# Interfaces.net
KiCad netlist of a schematic drawn in Altium Designer
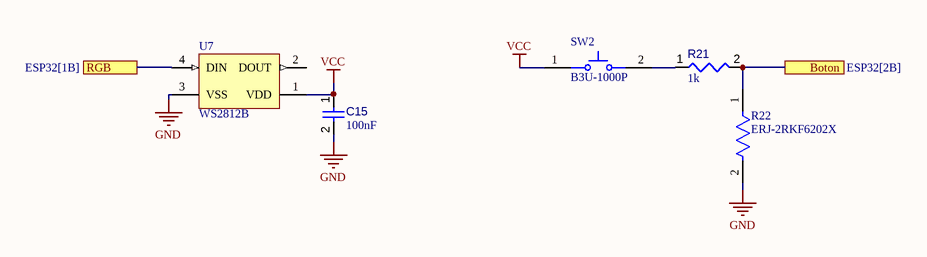
[diagram p0: Interfaces.SchDoc]

(export (version "E")
  (design (tool "Eeschema 10.0.6"))
  (components
    (comp (ref "C15")
      (value "100nF")
      (footprint "CAPC1005X56X25LL10T15")
      (description "Chip Capacitor, 0.1 uF, +/- 5%, 16 V, 0402 (1005 Metric)")
      (fields (field (name "TOLERANCE") "5%") (field (name "Comment") "Capacitor 0.1 uF +/- 5% 16 V 0402"))
      (libsource (lib "Own Worskpace") (part "CAP-NP-2"))
    )
    (comp (ref "R21")
      (value "1k")
      (footprint "RESC0402(1005)_L")
      (description "Chip Resistor, 1 kOhms, +/-5 %, 63 mW, -55 to 155 degC, 0402")
      (fields (field (name "TOLERANCE") "5%") (field (name "POWER") "63mW"))
      (libsource (lib "Own Worskpace") (part "RES-2"))
    )
    (comp (ref "R22")
      (value "ERJ-2RKF6202X")
      (footprint "FP-ERJ2RK-MFG")
      (fields (field (name "TOLERANCE") "1%"))
      (libsource (lib "Altium Content Vault") (part "1029c3af85768c4190bb7ad29bc67b5"))
    )
    (comp (ref "SW2")
      (value "B3U-1000P")
      (footprint "OMRON-B3U-1000_V")
      (description "Tactile Switch, SPST-NO, 0.05 A, 12 V, -25 to 70 degC, 2-Pin SMD, RoHS, Tape and Reel")
      (fields (field (name "MANUFACTURER") "Omron Electronic Components"))
      (libsource (lib "Own Worskpace") (part "SW-SPST-NO-2"))
    )
    (comp (ref "U7")
      (value "WS2812B")
      (footprint "ADAI-WS2812B_V")
      (fields (field (name "MANUFACTURER") "Adafruit Industries"))
      (libsource (lib "Own Worskpace") (part "ADAI-WS2812B-4"))
    )
  )
  (nets
    (net (code "1") (name "/Boton") (class "Default")
      (node (ref "R21") (pin "2") (pinfunction "2_2") (pintype "passive"))
      (node (ref "R22") (pin "1") (pinfunction "1_1") (pintype "passive"))
    )
    (net (code "2") (name "/RGB") (class "Default")
      (node (ref "U7") (pin "4") (pinfunction "DIN_4") (pintype "input"))
    )
    (net (code "3") (name "GND") (class "Default")
      (node (ref "C15") (pin "2") (pinfunction "2_2") (pintype "passive"))
      (node (ref "R22") (pin "2") (pinfunction "2_2") (pintype "passive"))
      (node (ref "U7") (pin "3") (pinfunction "VSS_3") (pintype "power_in"))
    )
    (net (code "4") (name "Net-(R21-Pad1)") (class "Default")
      (node (ref "R21") (pin "1") (pinfunction "1_1") (pintype "passive"))
      (node (ref "SW2") (pin "2") (pinfunction "2_2") (pintype "passive"))
    )
    (net (code "5") (name "VCC") (class "Default")
      (node (ref "C15") (pin "1") (pinfunction "1_1") (pintype "passive"))
      (node (ref "SW2") (pin "1") (pinfunction "1_1") (pintype "passive"))
      (node (ref "U7") (pin "1") (pinfunction "VDD_1") (pintype "power_in"))
    )
    (net (code "6") (name "unconnected-(U7-DOUT-Pad2)") (class "Default")
      (node (ref "U7") (pin "2") (pinfunction "DOUT_2") (pintype "output"))
    )
  )
)
